# right.net
KiCad netlist of a schematic drawn in EAGLE
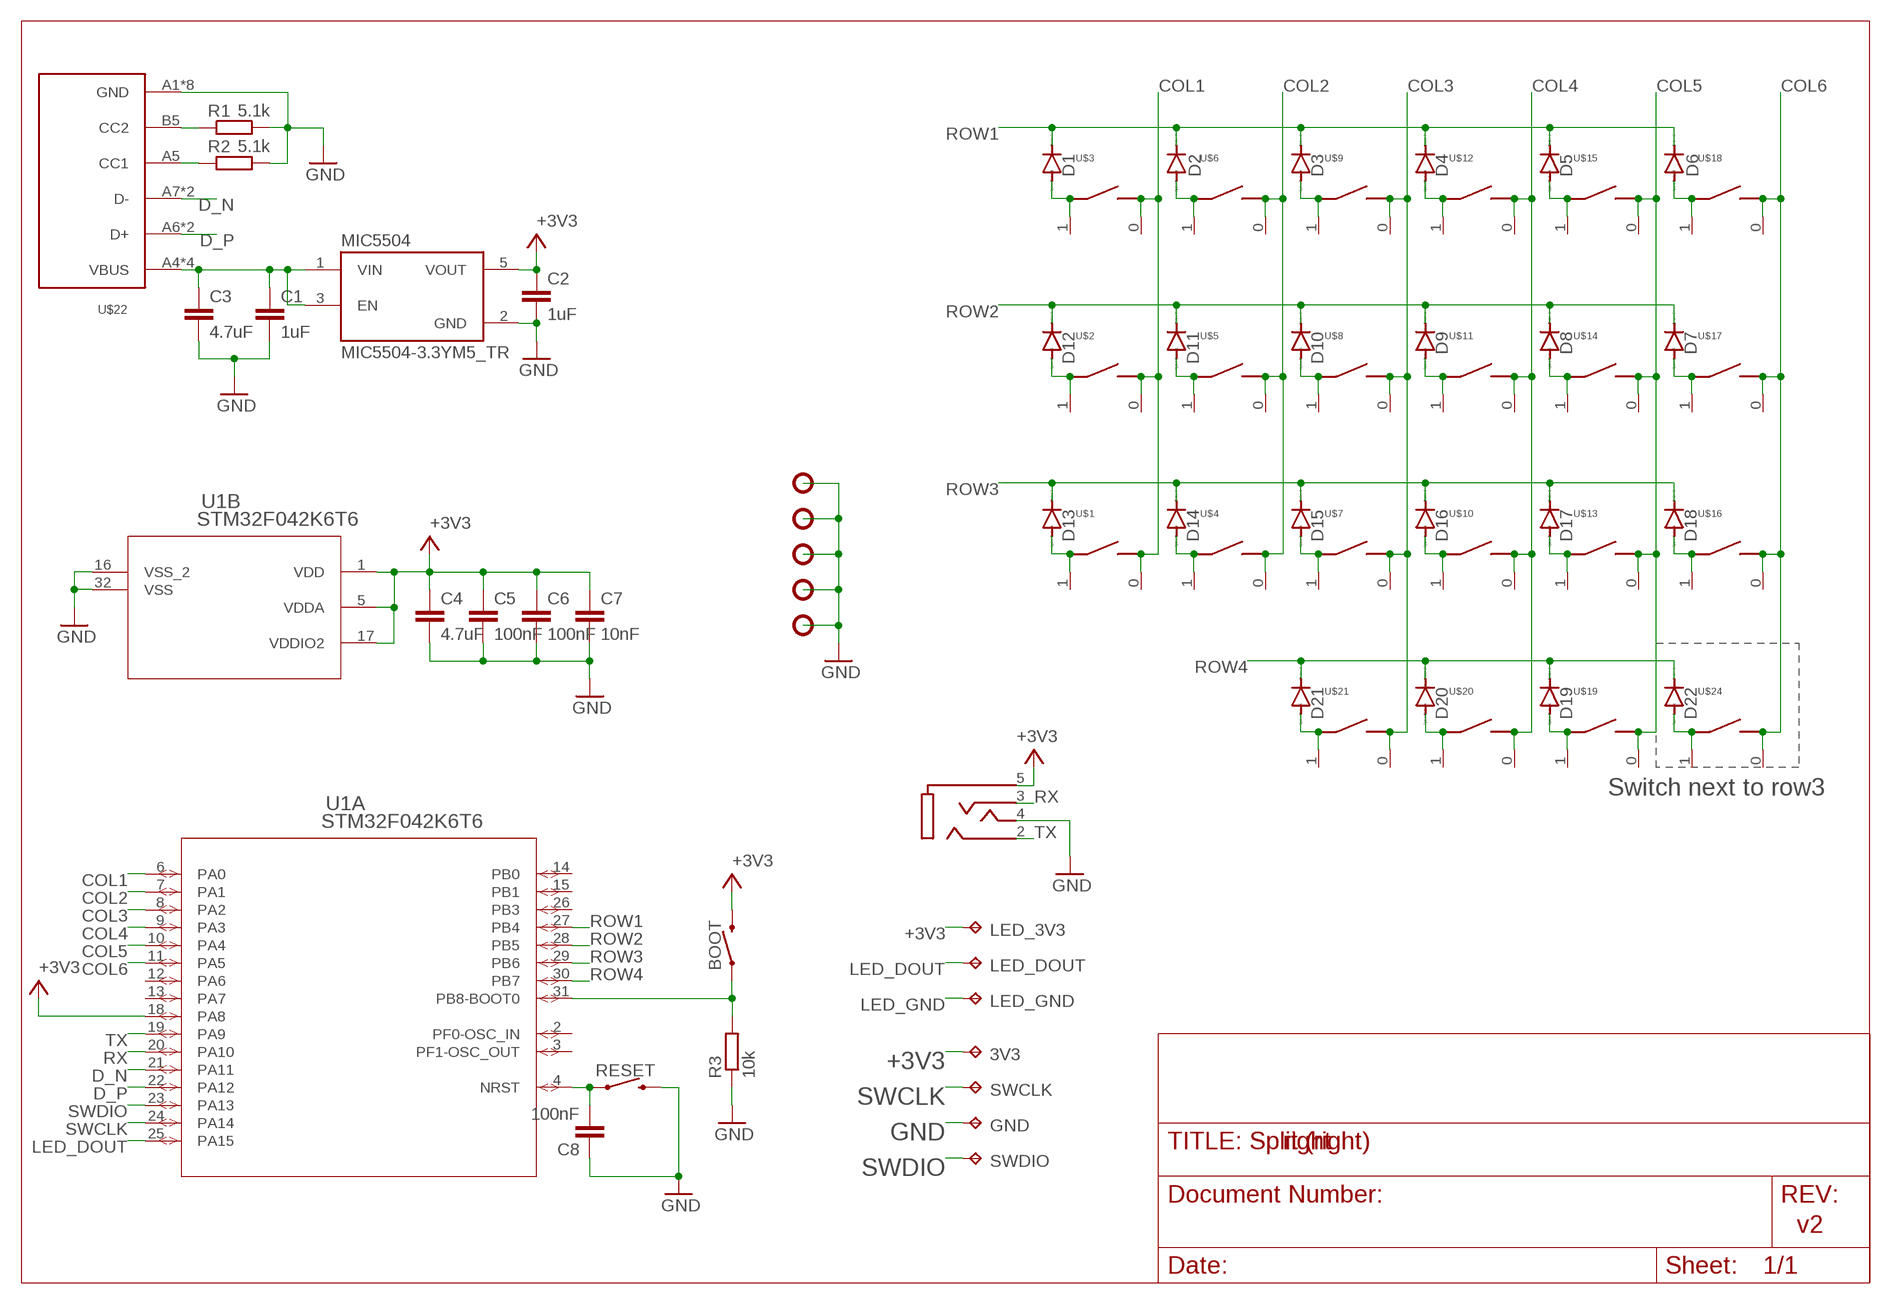
[diagram p0: schematic, sheet 1]

(export (version "E")
  (design (tool "Eeschema 10.0.6"))
  (components
    (comp (ref "3V3")
      (value "TPTP20R")
      (footprint "eagle-import:TP20R")
      (libsource (lib "eagle-import") (part "TPTP20R"))
    )
    (comp (ref "BOOT")
      (value "MOMENTARY-SWITCH-SPST-SMD-6.2MM-TALL")
      (footprint "eagle-import:TACTILE_SWITCH_SMD_6.2MM")
      (libsource (lib "eagle-import") (part "MOMENTARY-SWITCH-SPST-SMD-6.2MM-TALL"))
    )
    (comp (ref "C1")
      (value "1uF")
      (footprint "eagle-import:C0603")
      (libsource (lib "eagle-import") (part "C-EUC0603"))
    )
    (comp (ref "C2")
      (value "1uF")
      (footprint "eagle-import:C0603")
      (libsource (lib "eagle-import") (part "C-EUC0603"))
    )
    (comp (ref "C3")
      (value "4.7uF")
      (footprint "eagle-import:C0603")
      (libsource (lib "eagle-import") (part "C-EUC0603"))
    )
    (comp (ref "C4")
      (value "4.7uF")
      (footprint "eagle-import:C0603")
      (libsource (lib "eagle-import") (part "C-EUC0603"))
    )
    (comp (ref "C5")
      (value "100nF")
      (footprint "eagle-import:C0603")
      (libsource (lib "eagle-import") (part "C-EUC0603"))
    )
    (comp (ref "C6")
      (value "100nF")
      (footprint "eagle-import:C0603")
      (libsource (lib "eagle-import") (part "C-EUC0603"))
    )
    (comp (ref "C7")
      (value "10nF")
      (footprint "eagle-import:C0603")
      (libsource (lib "eagle-import") (part "C-EUC0603"))
    )
    (comp (ref "C8")
      (value "100nF")
      (footprint "eagle-import:C0603")
      (libsource (lib "eagle-import") (part "C-EUC0603"))
    )
    (comp (ref "D1")
      (value "DIODE-MINIMELF")
      (footprint "eagle-import:MINIMELF")
      (libsource (lib "eagle-import") (part "DIODE-MINIMELF"))
    )
    (comp (ref "D2")
      (value "DIODE-MINIMELF")
      (footprint "eagle-import:MINIMELF")
      (libsource (lib "eagle-import") (part "DIODE-MINIMELF"))
    )
    (comp (ref "D3")
      (value "DIODE-MINIMELF")
      (footprint "eagle-import:MINIMELF")
      (libsource (lib "eagle-import") (part "DIODE-MINIMELF"))
    )
    (comp (ref "D4")
      (value "DIODE-MINIMELF")
      (footprint "eagle-import:MINIMELF")
      (libsource (lib "eagle-import") (part "DIODE-MINIMELF"))
    )
    (comp (ref "D5")
      (value "DIODE-MINIMELF")
      (footprint "eagle-import:MINIMELF")
      (libsource (lib "eagle-import") (part "DIODE-MINIMELF"))
    )
    (comp (ref "D6")
      (value "DIODE-MINIMELF")
      (footprint "eagle-import:MINIMELF")
      (libsource (lib "eagle-import") (part "DIODE-MINIMELF"))
    )
    (comp (ref "D7")
      (value "DIODE-MINIMELF")
      (footprint "eagle-import:MINIMELF")
      (libsource (lib "eagle-import") (part "DIODE-MINIMELF"))
    )
    (comp (ref "D8")
      (value "DIODE-MINIMELF")
      (footprint "eagle-import:MINIMELF")
      (libsource (lib "eagle-import") (part "DIODE-MINIMELF"))
    )
    (comp (ref "D9")
      (value "DIODE-MINIMELF")
      (footprint "eagle-import:MINIMELF")
      (libsource (lib "eagle-import") (part "DIODE-MINIMELF"))
    )
    (comp (ref "D10")
      (value "DIODE-MINIMELF")
      (footprint "eagle-import:MINIMELF")
      (libsource (lib "eagle-import") (part "DIODE-MINIMELF"))
    )
    (comp (ref "D11")
      (value "DIODE-MINIMELF")
      (footprint "eagle-import:MINIMELF")
      (libsource (lib "eagle-import") (part "DIODE-MINIMELF"))
    )
    (comp (ref "D12")
      (value "DIODE-MINIMELF")
      (footprint "eagle-import:MINIMELF")
      (libsource (lib "eagle-import") (part "DIODE-MINIMELF"))
    )
    (comp (ref "D13")
      (value "DIODE-MINIMELF")
      (footprint "eagle-import:MINIMELF")
      (libsource (lib "eagle-import") (part "DIODE-MINIMELF"))
    )
    (comp (ref "D14")
      (value "DIODE-MINIMELF")
      (footprint "eagle-import:MINIMELF")
      (libsource (lib "eagle-import") (part "DIODE-MINIMELF"))
    )
    (comp (ref "D15")
      (value "DIODE-MINIMELF")
      (footprint "eagle-import:MINIMELF")
      (libsource (lib "eagle-import") (part "DIODE-MINIMELF"))
    )
    (comp (ref "D16")
      (value "DIODE-MINIMELF")
      (footprint "eagle-import:MINIMELF")
      (libsource (lib "eagle-import") (part "DIODE-MINIMELF"))
    )
    (comp (ref "D17")
      (value "DIODE-MINIMELF")
      (footprint "eagle-import:MINIMELF")
      (libsource (lib "eagle-import") (part "DIODE-MINIMELF"))
    )
    (comp (ref "D18")
      (value "DIODE-MINIMELF")
      (footprint "eagle-import:MINIMELF")
      (libsource (lib "eagle-import") (part "DIODE-MINIMELF"))
    )
    (comp (ref "D19")
      (value "DIODE-MINIMELF")
      (footprint "eagle-import:MINIMELF")
      (libsource (lib "eagle-import") (part "DIODE-MINIMELF"))
    )
    (comp (ref "D20")
      (value "DIODE-MINIMELF")
      (footprint "eagle-import:MINIMELF")
      (libsource (lib "eagle-import") (part "DIODE-MINIMELF"))
    )
    (comp (ref "D21")
      (value "DIODE-MINIMELF")
      (footprint "eagle-import:MINIMELF")
      (libsource (lib "eagle-import") (part "DIODE-MINIMELF"))
    )
    (comp (ref "D22")
      (value "DIODE-MINIMELF")
      (footprint "eagle-import:MINIMELF")
      (libsource (lib "eagle-import") (part "DIODE-MINIMELF"))
    )
    (comp (ref "GND")
      (value "TPTP20R")
      (footprint "eagle-import:TP20R")
      (libsource (lib "eagle-import") (part "TPTP20R"))
    )
    (comp (ref "LED_3V3")
      (value "TPTP20R")
      (footprint "eagle-import:TP20R")
      (libsource (lib "eagle-import") (part "TPTP20R"))
    )
    (comp (ref "LED_DOUT")
      (value "TPTP20R")
      (footprint "eagle-import:TP20R")
      (libsource (lib "eagle-import") (part "TPTP20R"))
    )
    (comp (ref "LED_GND")
      (value "TPTP20R")
      (footprint "eagle-import:TP20R")
      (libsource (lib "eagle-import") (part "TPTP20R"))
    )
    (comp (ref "MIC5504")
      (value "MIC5504-3.3YM5_TR")
      (footprint "eagle-import:SOT95P280X145-5N")
      (fields (field (name "MF") "Microchip") (field (name "MP") "MIC5504-3.3YM5 TR"))
      (libsource (lib "eagle-import") (part "MIC5504-3.3YM5_TR"))
    )
    (comp (ref "R1")
      (value "5.1k")
      (footprint "eagle-import:R0603")
      (libsource (lib "eagle-import") (part "R-EU_R0603"))
    )
    (comp (ref "R2")
      (value "5.1k")
      (footprint "eagle-import:R0603")
      (libsource (lib "eagle-import") (part "R-EU_R0603"))
    )
    (comp (ref "R3")
      (value "10k")
      (footprint "eagle-import:R0603")
      (libsource (lib "eagle-import") (part "R-EU_R0603"))
    )
    (comp (ref "RESET")
      (value "MOMENTARY-SWITCH-SPST-SMD-6.2MM-TALL")
      (footprint "eagle-import:TACTILE_SWITCH_SMD_6.2MM")
      (libsource (lib "eagle-import") (part "MOMENTARY-SWITCH-SPST-SMD-6.2MM-TALL"))
    )
    (comp (ref "SWCLK")
      (value "TPTP20R")
      (footprint "eagle-import:TP20R")
      (libsource (lib "eagle-import") (part "TPTP20R"))
    )
    (comp (ref "SWDIO")
      (value "TPTP20R")
      (footprint "eagle-import:TP20R")
      (libsource (lib "eagle-import") (part "TPTP20R"))
    )
    (comp (ref "U$1")
      (value "CHOC-CHOC-1U")
      (footprint "eagle-import:CHOC-1U")
      (libsource (lib "eagle-import") (part "CHOC-CHOC-1U"))
    )
    (comp (ref "U$2")
      (value "CHOC-CHOC-1U")
      (footprint "eagle-import:CHOC-1U")
      (libsource (lib "eagle-import") (part "CHOC-CHOC-1U"))
    )
    (comp (ref "U$3")
      (value "CHOC-CHOC-1U")
      (footprint "eagle-import:CHOC-1U")
      (libsource (lib "eagle-import") (part "CHOC-CHOC-1U"))
    )
    (comp (ref "U$4")
      (value "CHOC-CHOC-1U")
      (footprint "eagle-import:CHOC-1U")
      (libsource (lib "eagle-import") (part "CHOC-CHOC-1U"))
    )
    (comp (ref "U$5")
      (value "CHOC-CHOC-1U")
      (footprint "eagle-import:CHOC-1U")
      (libsource (lib "eagle-import") (part "CHOC-CHOC-1U"))
    )
    (comp (ref "U$6")
      (value "CHOC-CHOC-1U")
      (footprint "eagle-import:CHOC-1U")
      (libsource (lib "eagle-import") (part "CHOC-CHOC-1U"))
    )
    (comp (ref "U$7")
      (value "CHOC-CHOC-1U")
      (footprint "eagle-import:CHOC-1U")
      (libsource (lib "eagle-import") (part "CHOC-CHOC-1U"))
    )
    (comp (ref "U$8")
      (value "CHOC-CHOC-1U")
      (footprint "eagle-import:CHOC-1U")
      (libsource (lib "eagle-import") (part "CHOC-CHOC-1U"))
    )
    (comp (ref "U$9")
      (value "CHOC-CHOC-1U")
      (footprint "eagle-import:CHOC-1U")
      (libsource (lib "eagle-import") (part "CHOC-CHOC-1U"))
    )
    (comp (ref "U$10")
      (value "CHOC-CHOC-1U")
      (footprint "eagle-import:CHOC-1U")
      (libsource (lib "eagle-import") (part "CHOC-CHOC-1U"))
    )
    (comp (ref "U$11")
      (value "CHOC-CHOC-1U")
      (footprint "eagle-import:CHOC-1U")
      (libsource (lib "eagle-import") (part "CHOC-CHOC-1U"))
    )
    (comp (ref "U$12")
      (value "CHOC-CHOC-1U")
      (footprint "eagle-import:CHOC-1U")
      (libsource (lib "eagle-import") (part "CHOC-CHOC-1U"))
    )
    (comp (ref "U$13")
      (value "CHOC-CHOC-1U")
      (footprint "eagle-import:CHOC-1U")
      (libsource (lib "eagle-import") (part "CHOC-CHOC-1U"))
    )
    (comp (ref "U$14")
      (value "CHOC-CHOC-1U")
      (footprint "eagle-import:CHOC-1U")
      (libsource (lib "eagle-import") (part "CHOC-CHOC-1U"))
    )
    (comp (ref "U$15")
      (value "CHOC-CHOC-1U")
      (footprint "eagle-import:CHOC-1U")
      (libsource (lib "eagle-import") (part "CHOC-CHOC-1U"))
    )
    (comp (ref "U$16")
      (value "CHOC-CHOC-1U")
      (footprint "eagle-import:CHOC-1U")
      (libsource (lib "eagle-import") (part "CHOC-CHOC-1U"))
    )
    (comp (ref "U$17")
      (value "CHOC-CHOC-1U")
      (footprint "eagle-import:CHOC-1U")
      (libsource (lib "eagle-import") (part "CHOC-CHOC-1U"))
    )
    (comp (ref "U$18")
      (value "CHOC-CHOC-1U")
      (footprint "eagle-import:CHOC-1U")
      (libsource (lib "eagle-import") (part "CHOC-CHOC-1U"))
    )
    (comp (ref "U$19")
      (value "CHOC-CHOC-1U")
      (footprint "eagle-import:CHOC-1U")
      (libsource (lib "eagle-import") (part "CHOC-CHOC-1U"))
    )
    (comp (ref "U$20")
      (value "CHOC-CHOC-1U")
      (footprint "eagle-import:CHOC-1U")
      (libsource (lib "eagle-import") (part "CHOC-CHOC-1U"))
    )
    (comp (ref "U$21")
      (value "CHOC-CHOC-1U")
      (footprint "eagle-import:CHOC-1U")
      (libsource (lib "eagle-import") (part "CHOC-CHOC-1U"))
    )
    (comp (ref "U$22")
      (value "217B-AG01")
      (footprint "eagle-import:217B-AG01")
      (libsource (lib "eagle-import") (part "217B-AG01"))
    )
    (comp (ref "U$23")
      (value "PJ320A")
      (footprint "eagle-import:PJ320A")
      (libsource (lib "eagle-import") (part "PJ320A"))
    )
    (comp (ref "U$24")
      (value "CHOC-CHOC-1U")
      (footprint "eagle-import:CHOC-1U")
      (libsource (lib "eagle-import") (part "CHOC-CHOC-1U"))
    )
    (comp (ref "U$25")
      (value "SOCKET")
      (footprint "eagle-import:CHOC-SOCKET")
      (libsource (lib "eagle-import") (part "SOCKET"))
    )
    (comp (ref "U$26")
      (value "SOCKET")
      (footprint "eagle-import:CHOC-SOCKET")
      (libsource (lib "eagle-import") (part "SOCKET"))
    )
    (comp (ref "U$27")
      (value "SOCKET")
      (footprint "eagle-import:CHOC-SOCKET")
      (libsource (lib "eagle-import") (part "SOCKET"))
    )
    (comp (ref "U$28")
      (value "SOCKET")
      (footprint "eagle-import:CHOC-SOCKET")
      (libsource (lib "eagle-import") (part "SOCKET"))
    )
    (comp (ref "U$29")
      (value "SOCKET")
      (footprint "eagle-import:CHOC-SOCKET")
      (libsource (lib "eagle-import") (part "SOCKET"))
    )
    (comp (ref "U$30")
      (value "SOCKET")
      (footprint "eagle-import:CHOC-SOCKET")
      (libsource (lib "eagle-import") (part "SOCKET"))
    )
    (comp (ref "U$31")
      (value "SOCKET")
      (footprint "eagle-import:CHOC-SOCKET")
      (libsource (lib "eagle-import") (part "SOCKET"))
    )
    (comp (ref "U$32")
      (value "SOCKET")
      (footprint "eagle-import:CHOC-SOCKET")
      (libsource (lib "eagle-import") (part "SOCKET"))
    )
    (comp (ref "U$33")
      (value "SOCKET")
      (footprint "eagle-import:CHOC-SOCKET")
      (libsource (lib "eagle-import") (part "SOCKET"))
    )
    (comp (ref "U$34")
      (value "SOCKET")
      (footprint "eagle-import:CHOC-SOCKET")
      (libsource (lib "eagle-import") (part "SOCKET"))
    )
    (comp (ref "U$35")
      (value "SOCKET")
      (footprint "eagle-import:CHOC-SOCKET")
      (libsource (lib "eagle-import") (part "SOCKET"))
    )
    (comp (ref "U$36")
      (value "SOCKET")
      (footprint "eagle-import:CHOC-SOCKET")
      (libsource (lib "eagle-import") (part "SOCKET"))
    )
    (comp (ref "U$37")
      (value "SOCKET")
      (footprint "eagle-import:CHOC-SOCKET")
      (libsource (lib "eagle-import") (part "SOCKET"))
    )
    (comp (ref "U$38")
      (value "SOCKET")
      (footprint "eagle-import:CHOC-SOCKET")
      (libsource (lib "eagle-import") (part "SOCKET"))
    )
    (comp (ref "U$39")
      (value "SOCKET")
      (footprint "eagle-import:CHOC-SOCKET")
      (libsource (lib "eagle-import") (part "SOCKET"))
    )
    (comp (ref "U$40")
      (value "SOCKET")
      (footprint "eagle-import:CHOC-SOCKET")
      (libsource (lib "eagle-import") (part "SOCKET"))
    )
    (comp (ref "U$41")
      (value "SOCKET")
      (footprint "eagle-import:CHOC-SOCKET")
      (libsource (lib "eagle-import") (part "SOCKET"))
    )
    (comp (ref "U$42")
      (value "SOCKET")
      (footprint "eagle-import:CHOC-SOCKET")
      (libsource (lib "eagle-import") (part "SOCKET"))
    )
    (comp (ref "U$43")
      (value "SOCKET")
      (footprint "eagle-import:CHOC-SOCKET")
      (libsource (lib "eagle-import") (part "SOCKET"))
    )
    (comp (ref "U$44")
      (value "SOCKET")
      (footprint "eagle-import:CHOC-SOCKET")
      (libsource (lib "eagle-import") (part "SOCKET"))
    )
    (comp (ref "U$45")
      (value "SOCKET")
      (footprint "eagle-import:CHOC-SOCKET")
      (libsource (lib "eagle-import") (part "SOCKET"))
    )
    (comp (ref "U$46")
      (value "SOCKET")
      (footprint "eagle-import:CHOC-SOCKET")
      (libsource (lib "eagle-import") (part "SOCKET"))
    )
    (comp (ref "U$47")
      (value "MOUNTING-PADHOLE-M2-OFFSET")
      (footprint "eagle-import:HOLE-M2-OFFSET")
      (libsource (lib "eagle-import") (part "MOUNTING-PADHOLE-M2-OFFSET"))
    )
    (comp (ref "U$48")
      (value "MOUNTING-PADHOLE-M2-OFFSET")
      (footprint "eagle-import:HOLE-M2-OFFSET")
      (libsource (lib "eagle-import") (part "MOUNTING-PADHOLE-M2-OFFSET"))
    )
    (comp (ref "U$49")
      (value "MOUNTING-PADHOLE-M2-OFFSET")
      (footprint "eagle-import:HOLE-M2-OFFSET")
      (libsource (lib "eagle-import") (part "MOUNTING-PADHOLE-M2-OFFSET"))
    )
    (comp (ref "U$50")
      (value "MOUNTING-PADHOLE-M2-OFFSET")
      (footprint "eagle-import:HOLE-M2-OFFSET")
      (libsource (lib "eagle-import") (part "MOUNTING-PADHOLE-M2-OFFSET"))
    )
    (comp (ref "U$51")
      (value "MOUNTING-PADHOLE-M2-OFFSET")
      (footprint "eagle-import:HOLE-M2-OFFSET")
      (libsource (lib "eagle-import") (part "MOUNTING-PADHOLE-M2-OFFSET"))
    )
    (comp (ref "U1")
      (value "STM32F042K6T6")
      (footprint "eagle-import:LQFP-32")
      (fields (field (name "COPYRIGHT") "Copyright (C) 2018 Accelerated Designs. All rights reserved"))
      (libsource (lib "eagle-import") (part "STM32F042K6T6"))
    )
  )
  (nets
    (net (code "1") (name "+3V3") (class "Default")
      (node (ref "3V3") (pin "TP") (pinfunction "TP_TP") (pintype "input"))
      (node (ref "BOOT") (pin "B2") (pinfunction "2_B2") (pintype "passive"))
      (node (ref "C2") (pin "1") (pinfunction "1_1") (pintype "passive"))
      (node (ref "C4") (pin "1") (pinfunction "1_1") (pintype "passive"))
      (node (ref "C5") (pin "1") (pinfunction "1_1") (pintype "passive"))
      (node (ref "C6") (pin "1") (pinfunction "1_1") (pintype "passive"))
      (node (ref "C7") (pin "1") (pinfunction "1_1") (pintype "passive"))
      (node (ref "LED_3V3") (pin "TP") (pinfunction "TP_TP") (pintype "input"))
      (node (ref "MIC5504") (pin "5") (pinfunction "VOUT_5") (pintype "output"))
      (node (ref "U$23") (pin "5") (pinfunction "5_5") (pintype "bidirectional"))
      (node (ref "U1") (pin "1") (pinfunction "VDD_1") (pintype "power_in"))
      (node (ref "U1") (pin "17") (pinfunction "VDDIO2_17") (pintype "power_in"))
      (node (ref "U1") (pin "18") (pinfunction "PA8_18") (pintype "bidirectional"))
      (node (ref "U1") (pin "5") (pinfunction "VDDA_5") (pintype "power_in"))
    )
    (net (code "2") (name "/COL1") (class "Default")
      (node (ref "U$1") (pin "1") (pinfunction "P1_1") (pintype "bidirectional"))
      (node (ref "U$2") (pin "1") (pinfunction "P1_1") (pintype "bidirectional"))
      (node (ref "U$25") (pin "0") (pinfunction "0_0") (pintype "bidirectional"))
      (node (ref "U$26") (pin "0") (pinfunction "0_0") (pintype "bidirectional"))
      (node (ref "U$3") (pin "1") (pinfunction "P1_1") (pintype "bidirectional"))
      (node (ref "U$30") (pin "0") (pinfunction "0_0") (pintype "bidirectional"))
      (node (ref "U1") (pin "6") (pinfunction "PA0_6") (pintype "bidirectional"))
    )
    (net (code "3") (name "/COL2") (class "Default")
      (node (ref "U$27") (pin "0") (pinfunction "0_0") (pintype "bidirectional"))
      (node (ref "U$31") (pin "0") (pinfunction "0_0") (pintype "bidirectional"))
      (node (ref "U$4") (pin "1") (pinfunction "P1_1") (pintype "bidirectional"))
      (node (ref "U$46") (pin "0") (pinfunction "0_0") (pintype "bidirectional"))
      (node (ref "U$5") (pin "1") (pinfunction "P1_1") (pintype "bidirectional"))
      (node (ref "U$6") (pin "1") (pinfunction "P1_1") (pintype "bidirectional"))
      (node (ref "U1") (pin "7") (pinfunction "PA1_7") (pintype "bidirectional"))
    )
    (net (code "4") (name "/COL3") (class "Default")
      (node (ref "U$21") (pin "1") (pinfunction "P1_1") (pintype "bidirectional"))
      (node (ref "U$28") (pin "0") (pinfunction "0_0") (pintype "bidirectional"))
      (node (ref "U$29") (pin "0") (pinfunction "0_0") (pintype "bidirectional"))
      (node (ref "U$32") (pin "0") (pinfunction "0_0") (pintype "bidirectional"))
      (node (ref "U$34") (pin "0") (pinfunction "0_0") (pintype "bidirectional"))
      (node (ref "U$7") (pin "1") (pinfunction "P1_1") (pintype "bidirectional"))
      (node (ref "U$8") (pin "1") (pinfunction "P1_1") (pintype "bidirectional"))
      (node (ref "U$9") (pin "1") (pinfunction "P1_1") (pintype "bidirectional"))
      (node (ref "U1") (pin "8") (pinfunction "PA2_8") (pintype "bidirectional"))
    )
    (net (code "5") (name "/COL4") (class "Default")
      (node (ref "U$10") (pin "1") (pinfunction "P1_1") (pintype "bidirectional"))
      (node (ref "U$11") (pin "1") (pinfunction "P1_1") (pintype "bidirectional"))
      (node (ref "U$12") (pin "1") (pinfunction "P1_1") (pintype "bidirectional"))
      (node (ref "U$20") (pin "1") (pinfunction "P1_1") (pintype "bidirectional"))
      (node (ref "U$33") (pin "0") (pinfunction "0_0") (pintype "bidirectional"))
      (node (ref "U$35") (pin "0") (pinfunction "0_0") (pintype "bidirectional"))
      (node (ref "U$41") (pin "0") (pinfunction "0_0") (pintype "bidirectional"))
      (node (ref "U$45") (pin "0") (pinfunction "0_0") (pintype "bidirectional"))
      (node (ref "U1") (pin "9") (pinfunction "PA3_9") (pintype "bidirectional"))
    )
    (net (code "6") (name "/COL5") (class "Default")
      (node (ref "U$13") (pin "1") (pinfunction "P1_1") (pintype "bidirectional"))
      (node (ref "U$14") (pin "1") (pinfunction "P1_1") (pintype "bidirectional"))
      (node (ref "U$15") (pin "1") (pinfunction "P1_1") (pintype "bidirectional"))
      (node (ref "U$19") (pin "1") (pinfunction "P1_1") (pintype "bidirectional"))
      (node (ref "U$36") (pin "0") (pinfunction "0_0") (pintype "bidirectional"))
      (node (ref "U$39") (pin "0") (pinfunction "0_0") (pintype "bidirectional"))
      (node (ref "U$40") (pin "0") (pinfunction "0_0") (pintype "bidirectional"))
      (node (ref "U$44") (pin "0") (pinfunction "0_0") (pintype "bidirectional"))
      (node (ref "U1") (pin "10") (pinfunction "PA4_10") (pintype "bidirectional"))
    )
    (net (code "7") (name "/COL6") (class "Default")
      (node (ref "U$16") (pin "1") (pinfunction "P1_1") (pintype "bidirectional"))
      (node (ref "U$17") (pin "1") (pinfunction "P1_1") (pintype "bidirectional"))
      (node (ref "U$18") (pin "1") (pinfunction "P1_1") (pintype "bidirectional"))
      (node (ref "U$24") (pin "1") (pinfunction "P1_1") (pintype "bidirectional"))
      (node (ref "U$37") (pin "0") (pinfunction "0_0") (pintype "bidirectional"))
      (node (ref "U$38") (pin "0") (pinfunction "0_0") (pintype "bidirectional"))
      (node (ref "U$42") (pin "0") (pinfunction "0_0") (pintype "bidirectional"))
      (node (ref "U$43") (pin "0") (pinfunction "0_0") (pintype "bidirectional"))
      (node (ref "U1") (pin "11") (pinfunction "PA5_11") (pintype "bidirectional"))
    )
    (net (code "8") (name "/D_N") (class "Default")
      (node (ref "U$22") (pin "A7") (pinfunction "D-_A7") (pintype "bidirectional"))
      (node (ref "U$22") (pin "B7") (pinfunction "D-_B7") (pintype "bidirectional"))
      (node (ref "U1") (pin "21") (pinfunction "PA11_21") (pintype "bidirectional"))
    )
    (net (code "9") (name "/D_P") (class "Default")
      (node (ref "U$22") (pin "A6") (pinfunction "D+_A6") (pintype "bidirectional"))
      (node (ref "U$22") (pin "B6") (pinfunction "D+_B6") (pintype "bidirectional"))
      (node (ref "U1") (pin "22") (pinfunction "PA12_22") (pintype "bidirectional"))
    )
    (net (code "10") (name "/LED_DOUT") (class "Default")
      (node (ref "LED_DOUT") (pin "TP") (pinfunction "TP_TP") (pintype "input"))
      (node (ref "U1") (pin "25") (pinfunction "PA15_25") (pintype "bidirectional"))
    )
    (net (code "11") (name "/LED_GND") (class "Default")
      (node (ref "LED_GND") (pin "TP") (pinfunction "TP_TP") (pintype "input"))
    )
    (net (code "12") (name "/ROW1") (class "Default")
      (node (ref "D1") (pin "C") (pinfunction "C_C") (pintype "passive"))
      (node (ref "D2") (pin "C") (pinfunction "C_C") (pintype "passive"))
      (node (ref "D3") (pin "C") (pinfunction "C_C") (pintype "passive"))
      (node (ref "D4") (pin "C") (pinfunction "C_C") (pintype "passive"))
      (node (ref "D5") (pin "C") (pinfunction "C_C") (pintype "passive"))
      (node (ref "D6") (pin "C") (pinfunction "C_C") (pintype "passive"))
      (node (ref "U1") (pin "27") (pinfunction "PB4_27") (pintype "bidirectional"))
    )
    (net (code "13") (name "/ROW2") (class "Default")
      (node (ref "D10") (pin "C") (pinfunction "C_C") (pintype "passive"))
      (node (ref "D11") (pin "C") (pinfunction "C_C") (pintype "passive"))
      (node (ref "D12") (pin "C") (pinfunction "C_C") (pintype "passive"))
      (node (ref "D7") (pin "C") (pinfunction "C_C") (pintype "passive"))
      (node (ref "D8") (pin "C") (pinfunction "C_C") (pintype "passive"))
      (node (ref "D9") (pin "C") (pinfunction "C_C") (pintype "passive"))
      (node (ref "U1") (pin "28") (pinfunction "PB5_28") (pintype "bidirectional"))
    )
    (net (code "14") (name "/ROW3") (class "Default")
      (node (ref "D13") (pin "C") (pinfunction "C_C") (pintype "passive"))
      (node (ref "D14") (pin "C") (pinfunction "C_C") (pintype "passive"))
      (node (ref "D15") (pin "C") (pinfunction "C_C") (pintype "passive"))
      (node (ref "D16") (pin "C") (pinfunction "C_C") (pintype "passive"))
      (node (ref "D17") (pin "C") (pinfunction "C_C") (pintype "passive"))
      (node (ref "D18") (pin "C") (pinfunction "C_C") (pintype "passive"))
      (node (ref "U1") (pin "29") (pinfunction "PB6_29") (pintype "bidirectional"))
    )
    (net (code "15") (name "/ROW4") (class "Default")
      (node (ref "D19") (pin "C") (pinfunction "C_C") (pintype "passive"))
      (node (ref "D20") (pin "C") (pinfunction "C_C") (pintype "passive"))
      (node (ref "D21") (pin "C") (pinfunction "C_C") (pintype "passive"))
      (node (ref "D22") (pin "C") (pinfunction "C_C") (pintype "passive"))
      (node (ref "U1") (pin "30") (pinfunction "PB7_30") (pintype "bidirectional"))
    )
    (net (code "16") (name "/RX") (class "Default")
      (node (ref "U$23") (pin "3") (pinfunction "3_3") (pintype "bidirectional"))
      (node (ref "U1") (pin "20") (pinfunction "PA10_20") (pintype "bidirectional"))
    )
    (net (code "17") (name "/SWCLK") (class "Default")
      (node (ref "SWCLK") (pin "TP") (pinfunction "TP_TP") (pintype "input"))
      (node (ref "U1") (pin "24") (pinfunction "PA14_24") (pintype "bidirectional"))
    )
    (net (code "18") (name "/SWDIO") (class "Default")
      (node (ref "SWDIO") (pin "TP") (pinfunction "TP_TP") (pintype "input"))
      (node (ref "U1") (pin "23") (pinfunction "PA13_23") (pintype "bidirectional"))
    )
    (net (code "19") (name "/TX") (class "Default")
      (node (ref "U$23") (pin "2") (pinfunction "2_2") (pintype "bidirectional"))
      (node (ref "U1") (pin "19") (pinfunction "PA9_19") (pintype "bidirectional"))
    )
    (net (code "20") (name "GND") (class "Default")
      (node (ref "C1") (pin "2") (pinfunction "2_2") (pintype "passive"))
      (node (ref "C2") (pin "2") (pinfunction "2_2") (pintype "passive"))
      (node (ref "C3") (pin "2") (pinfunction "2_2") (pintype "passive"))
      (node (ref "C4") (pin "2") (pinfunction "2_2") (pintype "passive"))
      (node (ref "C5") (pin "2") (pinfunction "2_2") (pintype "passive"))
      (node (ref "C6") (pin "2") (pinfunction "2_2") (pintype "passive"))
      (node (ref "C7") (pin "2") (pinfunction "2_2") (pintype "passive"))
      (node (ref "C8") (pin "1") (pinfunction "1_1") (pintype "passive"))
      (node (ref "GND") (pin "TP") (pinfunction "TP_TP") (pintype "input"))
      (node (ref "MIC5504") (pin "2") (pinfunction "GND_2") (pintype "power_in"))
      (node (ref "R1") (pin "2") (pinfunction "2_2") (pintype "passive"))
      (node (ref "R2") (pin "2") (pinfunction "2_2") (pintype "passive"))
      (node (ref "R3") (pin "1") (pinfunction "1_1") (pintype "passive"))
      (node (ref "RESET") (pin "B2") (pinfunction "2_B2") (pintype "passive"))
      (node (ref "U$22") (pin "A1") (pinfunction "GND_A1") (pintype "power_in"))
      (node (ref "U$22") (pin "A12") (pinfunction "GND_A12") (pintype "power_in"))
      (node (ref "U$22") (pin "B1") (pinfunction "GND_B1") (pintype "power_in"))
      (node (ref "U$22") (pin "B12") (pinfunction "GND_B12") (pintype "power_in"))
      (node (ref "U$22") (pin "SHELL") (pinfunction "GND_SHELL") (pintype "power_in"))
      (node (ref "U$22") (pin "SHELL1") (pinfunction "GND_SHELL1") (pintype "power_in"))
      (node (ref "U$22") (pin "SHELL2") (pinfunction "GND_SHELL2") (pintype "power_in"))
      (node (ref "U$22") (pin "SHELL3") (pinfunction "GND_SHELL3") (pintype "power_in"))
      (node (ref "U$23") (pin "4") (pinfunction "4_4") (pintype "bidirectional"))
      (node (ref "U$47") (pin "P$1") (pinfunction "P_P$1") (pintype "bidirectional"))
      (node (ref "U$48") (pin "P$1") (pinfunction "P_P$1") (pintype "bidirectional"))
      (node (ref "U$49") (pin "P$1") (pinfunction "P_P$1") (pintype "bidirectional"))
      (node (ref "U$50") (pin "P$1") (pinfunction "P_P$1") (pintype "bidirectional"))
      (node (ref "U$51") (pin "P$1") (pinfunction "P_P$1") (pintype "bidirectional"))
      (node (ref "U1") (pin "16") (pinfunction "VSS_2_16") (pintype "power_in"))
      (node (ref "U1") (pin "32") (pinfunction "VSS_32") (pintype "power_in"))
    )
    (net (code "21") (name "Net-(BOOT-1)") (class "Default")
      (node (ref "BOOT") (pin "A2") (pinfunction "1_A2") (pintype "passive"))
      (node (ref "R3") (pin "2") (pinfunction "2_2") (pintype "passive"))
      (node (ref "U1") (pin "31") (pinfunction "PB8-BOOT0_31") (pintype "bidirectional"))
    )
    (net (code "22") (name "Net-(MIC5504-EN)") (class "Default")
      (node (ref "C1") (pin "1") (pinfunction "1_1") (pintype "passive"))
      (node (ref "C3") (pin "1") (pinfunction "1_1") (pintype "passive"))
      (node (ref "MIC5504") (pin "1") (pinfunction "VIN_1") (pintype "input"))
      (node (ref "MIC5504") (pin "3") (pinfunction "EN_3") (pintype "input"))
      (node (ref "U$22") (pin "A4") (pinfunction "VBUS_A4") (pintype "power_in"))
      (node (ref "U$22") (pin "A9") (pinfunction "VBUS_A9") (pintype "power_in"))
      (node (ref "U$22") (pin "B4") (pinfunction "VBUS_B4") (pintype "power_in"))
      (node (ref "U$22") (pin "B9") (pinfunction "VBUS_B9") (pintype "power_in"))
    )
    (net (code "23") (name "Net-(RESET-1)") (class "Default")
      (node (ref "C8") (pin "2") (pinfunction "2_2") (pintype "passive"))
      (node (ref "RESET") (pin "A2") (pinfunction "1_A2") (pintype "passive"))
      (node (ref "U1") (pin "4") (pinfunction "NRST_4") (pintype "bidirectional"))
    )
    (net (code "24") (name "Net-(U$1-P0)") (class "Default")
      (node (ref "D13") (pin "A") (pinfunction "A_A") (pintype "passive"))
      (node (ref "U$1") (pin "0") (pinfunction "P0_0") (pintype "bidirectional"))
      (node (ref "U$30") (pin "1") (pinfunction "1_1") (pintype "bidirectional"))
    )
    (net (code "25") (name "Net-(U$2-P0)") (class "Default")
      (node (ref "D12") (pin "A") (pinfunction "A_A") (pintype "passive"))
      (node (ref "U$2") (pin "0") (pinfunction "P0_0") (pintype "bidirectional"))
      (node (ref "U$25") (pin "1") (pinfunction "1_1") (pintype "bidirectional"))
    )
    (net (code "26") (name "Net-(U$3-P0)") (class "Default")
      (node (ref "D1") (pin "A") (pinfunction "A_A") (pintype "passive"))
      (node (ref "U$26") (pin "1") (pinfunction "1_1") (pintype "bidirectional"))
      (node (ref "U$3") (pin "0") (pinfunction "P0_0") (pintype "bidirectional"))
    )
    (net (code "27") (name "Net-(U$4-P0)") (class "Default")
      (node (ref "D14") (pin "A") (pinfunction "A_A") (pintype "passive"))
      (node (ref "U$31") (pin "1") (pinfunction "1_1") (pintype "bidirectional"))
      (node (ref "U$4") (pin "0") (pinfunction "P0_0") (pintype "bidirectional"))
    )
    (net (code "28") (name "Net-(U$5-P0)") (class "Default")
      (node (ref "D11") (pin "A") (pinfunction "A_A") (pintype "passive"))
      (node (ref "U$46") (pin "1") (pinfunction "1_1") (pintype "bidirectional"))
      (node (ref "U$5") (pin "0") (pinfunction "P0_0") (pintype "bidirectional"))
    )
    (net (code "29") (name "Net-(U$6-P0)") (class "Default")
      (node (ref "D2") (pin "A") (pinfunction "A_A") (pintype "passive"))
      (node (ref "U$27") (pin "1") (pinfunction "1_1") (pintype "bidirectional"))
      (node (ref "U$6") (pin "0") (pinfunction "P0_0") (pintype "bidirectional"))
    )
    (net (code "30") (name "Net-(U$7-P0)") (class "Default")
      (node (ref "D15") (pin "A") (pinfunction "A_A") (pintype "passive"))
      (node (ref "U$32") (pin "1") (pinfunction "1_1") (pintype "bidirectional"))
      (node (ref "U$7") (pin "0") (pinfunction "P0_0") (pintype "bidirectional"))
    )
    (net (code "31") (name "Net-(U$8-P0)") (class "Default")
      (node (ref "D10") (pin "A") (pinfunction "A_A") (pintype "passive"))
      (node (ref "U$29") (pin "1") (pinfunction "1_1") (pintype "bidirectional"))
      (node (ref "U$8") (pin "0") (pinfunction "P0_0") (pintype "bidirectional"))
    )
    (net (code "32") (name "Net-(U$9-P0)") (class "Default")
      (node (ref "D3") (pin "A") (pinfunction "A_A") (pintype "passive"))
      (node (ref "U$28") (pin "1") (pinfunction "1_1") (pintype "bidirectional"))
      (node (ref "U$9") (pin "0") (pinfunction "P0_0") (pintype "bidirectional"))
    )
    (net (code "33") (name "Net-(U$10-P0)") (class "Default")
      (node (ref "D16") (pin "A") (pinfunction "A_A") (pintype "passive"))
      (node (ref "U$10") (pin "0") (pinfunction "P0_0") (pintype "bidirectional"))
      (node (ref "U$33") (pin "1") (pinfunction "1_1") (pintype "bidirectional"))
    )
    (net (code "34") (name "Net-(U$11-P0)") (class "Default")
      (node (ref "D9") (pin "A") (pinfunction "A_A") (pintype "passive"))
      (node (ref "U$11") (pin "0") (pinfunction "P0_0") (pintype "bidirectional"))
      (node (ref "U$41") (pin "1") (pinfunction "1_1") (pintype "bidirectional"))
    )
    (net (code "35") (name "Net-(U$12-P0)") (class "Default")
      (node (ref "D4") (pin "A") (pinfunction "A_A") (pintype "passive"))
      (node (ref "U$12") (pin "0") (pinfunction "P0_0") (pintype "bidirectional"))
      (node (ref "U$45") (pin "1") (pinfunction "1_1") (pintype "bidirectional"))
    )
    (net (code "36") (name "Net-(U$13-P0)") (class "Default")
      (node (ref "D17") (pin "A") (pinfunction "A_A") (pintype "passive"))
      (node (ref "U$13") (pin "0") (pinfunction "P0_0") (pintype "bidirectional"))
      (node (ref "U$39") (pin "1") (pinfunction "1_1") (pintype "bidirectional"))
    )
    (net (code "37") (name "Net-(U$14-P0)") (class "Default")
      (node (ref "D8") (pin "A") (pinfunction "A_A") (pintype "passive"))
      (node (ref "U$14") (pin "0") (pinfunction "P0_0") (pintype "bidirectional"))
      (node (ref "U$40") (pin "1") (pinfunction "1_1") (pintype "bidirectional"))
    )
    (net (code "38") (name "Net-(U$15-P0)") (class "Default")
      (node (ref "D5") (pin "A") (pinfunction "A_A") (pintype "passive"))
      (node (ref "U$15") (pin "0") (pinfunction "P0_0") (pintype "bidirectional"))
      (node (ref "U$44") (pin "1") (pinfunction "1_1") (pintype "bidirectional"))
    )
    (net (code "39") (name "Net-(U$16-P0)") (class "Default")
      (node (ref "D18") (pin "A") (pinfunction "A_A") (pintype "passive"))
      (node (ref "U$16") (pin "0") (pinfunction "P0_0") (pintype "bidirectional"))
      (node (ref "U$38") (pin "1") (pinfunction "1_1") (pintype "bidirectional"))
    )
    (net (code "40") (name "Net-(U$17-P0)") (class "Default")
      (node (ref "D7") (pin "A") (pinfunction "A_A") (pintype "passive"))
      (node (ref "U$17") (pin "0") (pinfunction "P0_0") (pintype "bidirectional"))
      (node (ref "U$42") (pin "1") (pinfunction "1_1") (pintype "bidirectional"))
    )
    (net (code "41") (name "Net-(U$18-P0)") (class "Default")
      (node (ref "D6") (pin "A") (pinfunction "A_A") (pintype "passive"))
      (node (ref "U$18") (pin "0") (pinfunction "P0_0") (pintype "bidirectional"))
      (node (ref "U$43") (pin "1") (pinfunction "1_1") (pintype "bidirectional"))
    )
    (net (code "42") (name "Net-(U$19-P0)") (class "Default")
      (node (ref "D19") (pin "A") (pinfunction "A_A") (pintype "passive"))
      (node (ref "U$19") (pin "0") (pinfunction "P0_0") (pintype "bidirectional"))
      (node (ref "U$36") (pin "1") (pinfunction "1_1") (pintype "bidirectional"))
    )
    (net (code "43") (name "Net-(U$20-P0)") (class "Default")
      (node (ref "D20") (pin "A") (pinfunction "A_A") (pintype "passive"))
      (node (ref "U$20") (pin "0") (pinfunction "P0_0") (pintype "bidirectional"))
      (node (ref "U$35") (pin "1") (pinfunction "1_1") (pintype "bidirectional"))
    )
    (net (code "44") (name "Net-(U$21-P0)") (class "Default")
      (node (ref "D21") (pin "A") (pinfunction "A_A") (pintype "passive"))
      (node (ref "U$21") (pin "0") (pinfunction "P0_0") (pintype "bidirectional"))
      (node (ref "U$34") (pin "1") (pinfunction "1_1") (pintype "bidirectional"))
    )
    (net (code "45") (name "Net-(U$22-CC1)") (class "Default")
      (node (ref "R2") (pin "1") (pinfunction "1_1") (pintype "passive"))
      (node (ref "U$22") (pin "A5") (pinfunction "CC1_A5") (pintype "bidirectional"))
    )
    (net (code "46") (name "Net-(U$22-CC2)") (class "Default")
      (node (ref "R1") (pin "1") (pinfunction "1_1") (pintype "passive"))
      (node (ref "U$22") (pin "B5") (pinfunction "CC2_B5") (pintype "bidirectional"))
    )
    (net (code "47") (name "Net-(U$24-P0)") (class "Default")
      (node (ref "D22") (pin "A") (pinfunction "A_A") (pintype "passive"))
      (node (ref "U$24") (pin "0") (pinfunction "P0_0") (pintype "bidirectional"))
      (node (ref "U$37") (pin "1") (pinfunction "1_1") (pintype "bidirectional"))
    )
    (net (code "48") (name "unconnected-(U1A-PA6-Pad12)") (class "Default")
      (node (ref "U1") (pin "12") (pinfunction "PA6_12") (pintype "bidirectional"))
    )
    (net (code "49") (name "unconnected-(U1A-PA7-Pad13)") (class "Default")
      (node (ref "U1") (pin "13") (pinfunction "PA7_13") (pintype "bidirectional"))
    )
    (net (code "50") (name "unconnected-(U1A-PB0-Pad14)") (class "Default")
      (node (ref "U1") (pin "14") (pinfunction "PB0_14") (pintype "bidirectional"))
    )
    (net (code "51") (name "unconnected-(U1A-PB1-Pad15)") (class "Default")
      (node (ref "U1") (pin "15") (pinfunction "PB1_15") (pintype "bidirectional"))
    )
    (net (code "52") (name "unconnected-(U1A-PB3-Pad26)") (class "Default")
      (node (ref "U1") (pin "26") (pinfunction "PB3_26") (pintype "bidirectional"))
    )
    (net (code "53") (name "unconnected-(U1A-PF0-OSC_IN-Pad2)") (class "Default")
      (node (ref "U1") (pin "2") (pinfunction "PF0-OSC_IN_2") (pintype "bidirectional"))
    )
    (net (code "54") (name "unconnected-(U1A-PF1-OSC_OUT-Pad3)") (class "Default")
      (node (ref "U1") (pin "3") (pinfunction "PF1-OSC_OUT_3") (pintype "bidirectional"))
    )
  )
)
